# JOYSTICK_LED.net
KiCad netlist of a schematic drawn in Altium Designer
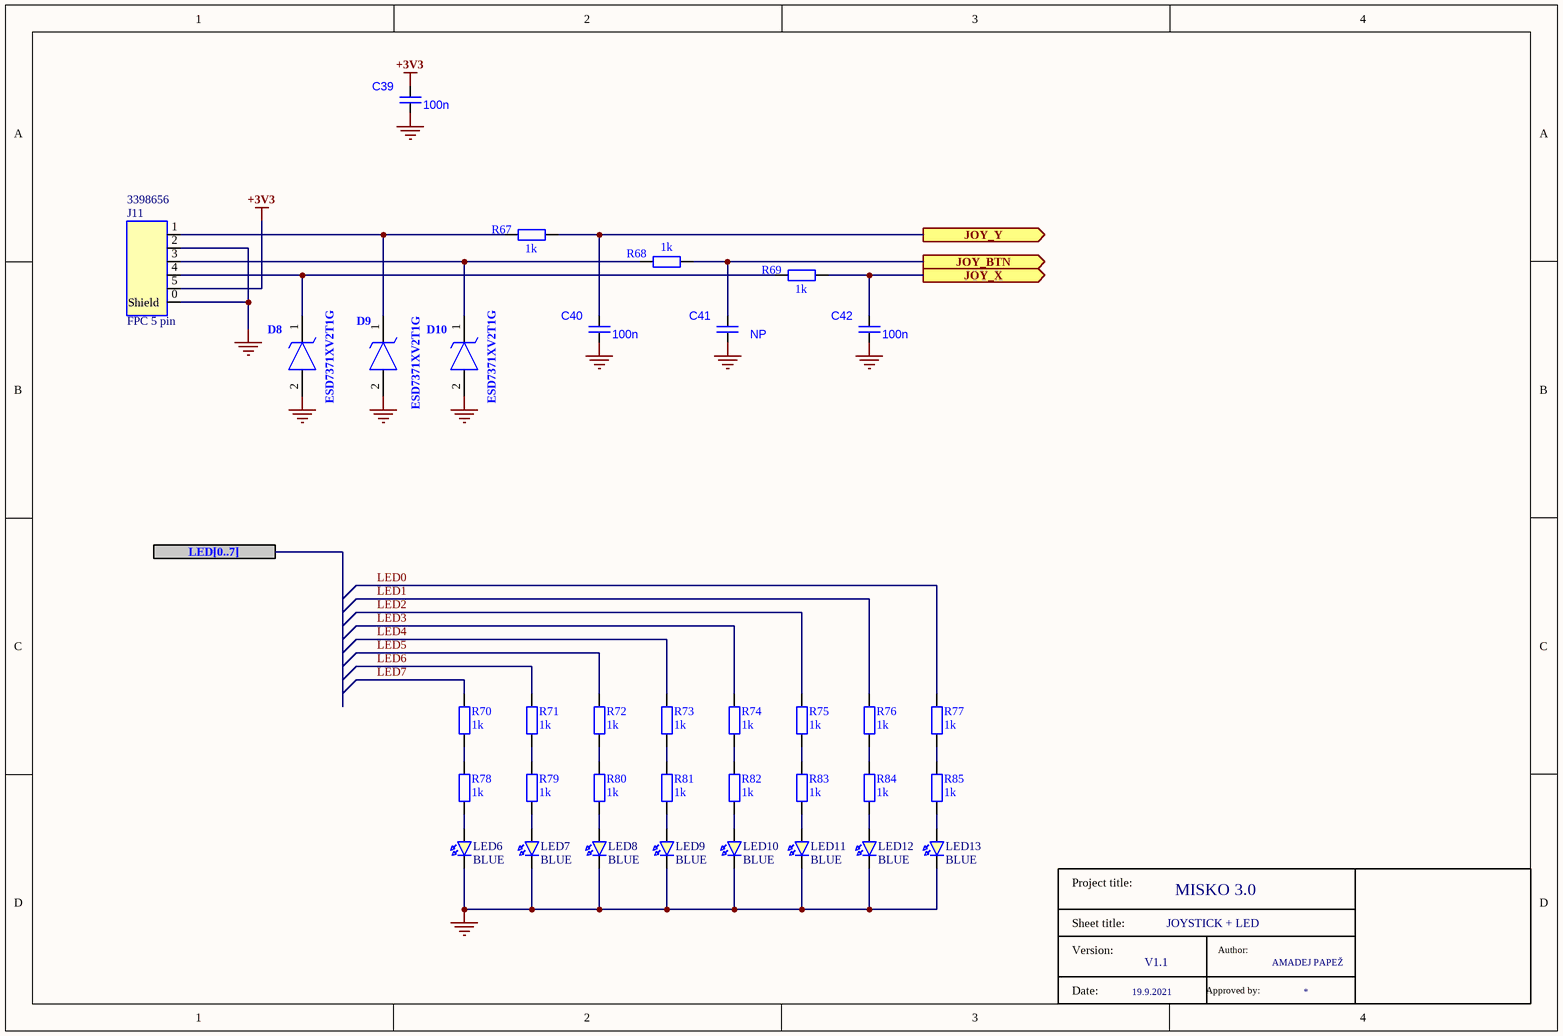
[diagram p0: JOYSTICK + LED.SchDoc]

(export (version "E")
  (design (tool "Eeschema 10.0.6"))
  (components
    (comp (ref "C39")
      (value "100n")
      (footprint "C0603")
      (description "Capacitor")
      (libsource (lib "MISKO3_V6") (part "C"))
    )
    (comp (ref "C40")
      (value "100n")
      (footprint "C0603")
      (description "Capacitor")
      (libsource (lib "MISKO3_V6") (part "C"))
    )
    (comp (ref "C41")
      (value "NP")
      (footprint "C0603")
      (description "Capacitor")
      (libsource (lib "MISKO3_V6") (part "C"))
    )
    (comp (ref "C42")
      (value "100n")
      (footprint "C0603")
      (description "Capacitor")
      (libsource (lib "MISKO3_V6") (part "C"))
    )
    (comp (ref "D8")
      (value "ESD7371XV2T1G")
      (footprint "SOD1608X70N")
      (description "TVS Diode (Uni-directional)")
      (fields (field (name "MOUSER PART NUMBER") "863-ESD7371XV2T1G"))
      (libsource (lib "MISKO3_V6") (part "ESD7371XV2T1G"))
    )
    (comp (ref "D9")
      (value "ESD7371XV2T1G")
      (footprint "SOD1608X70N")
      (description "TVS Diode (Uni-directional)")
      (fields (field (name "MOUSER PART NUMBER") "863-ESD7371XV2T1G"))
      (libsource (lib "MISKO3_V6") (part "ESD7371XV2T1G"))
    )
    (comp (ref "D10")
      (value "ESD7371XV2T1G")
      (footprint "SOD1608X70N")
      (description "TVS Diode (Uni-directional)")
      (fields (field (name "MOUSER PART NUMBER") "863-ESD7371XV2T1G"))
      (libsource (lib "MISKO3_V6") (part "ESD7371XV2T1G"))
    )
    (comp (ref "J11")
      (value "FPC 5 pin")
      (footprint "FPC 1734839-5")
      (description "TE connectivity  FPC 5 pin 0.5 mm ZIF top contact female connector 1734839-5")
      (fields (field (name "SUPPLIER PART NUMBER 1") "3398656"))
      (libsource (lib "MISKO3_V6") (part "FPC 1734839-5"))
    )
    (comp (ref "LED6")
      (value "BLUE")
      (footprint "LED1206")
      (description "LED")
      (libsource (lib "MISKO3_V6") (part "LED"))
    )
    (comp (ref "LED7")
      (value "BLUE")
      (footprint "LED1206")
      (description "LED")
      (libsource (lib "MISKO3_V6") (part "LED"))
    )
    (comp (ref "LED8")
      (value "BLUE")
      (footprint "LED1206")
      (description "LED")
      (libsource (lib "MISKO3_V6") (part "LED"))
    )
    (comp (ref "LED9")
      (value "BLUE")
      (footprint "LED1206")
      (description "LED")
      (libsource (lib "MISKO3_V6") (part "LED"))
    )
    (comp (ref "LED10")
      (value "BLUE")
      (footprint "LED1206")
      (description "LED")
      (libsource (lib "MISKO3_V6") (part "LED"))
    )
    (comp (ref "LED11")
      (value "BLUE")
      (footprint "LED1206")
      (description "LED")
      (libsource (lib "MISKO3_V6") (part "LED"))
    )
    (comp (ref "LED12")
      (value "BLUE")
      (footprint "LED1206")
      (description "LED")
      (libsource (lib "MISKO3_V6") (part "LED"))
    )
    (comp (ref "LED13")
      (value "BLUE")
      (footprint "LED1206")
      (description "LED")
      (libsource (lib "MISKO3_V6") (part "LED"))
    )
    (comp (ref "R67")
      (value "1k")
      (footprint "R1608_0603I_L")
      (description "R")
      (libsource (lib "MISKO3_V6") (part "R"))
    )
    (comp (ref "R68")
      (value "1k")
      (footprint "R1608_0603I_L")
      (description "R")
      (libsource (lib "MISKO3_V6") (part "R"))
    )
    (comp (ref "R69")
      (value "1k")
      (footprint "R1608_0603I_L")
      (description "R")
      (libsource (lib "MISKO3_V6") (part "R"))
    )
    (comp (ref "R70")
      (value "1k")
      (footprint "R1608_0603I_L")
      (description "R")
      (libsource (lib "MISKO3_V6") (part "R"))
    )
    (comp (ref "R71")
      (value "1k")
      (footprint "R1608_0603I_L")
      (description "R")
      (libsource (lib "MISKO3_V6") (part "R"))
    )
    (comp (ref "R72")
      (value "1k")
      (footprint "R1608_0603I_L")
      (description "R")
      (libsource (lib "MISKO3_V6") (part "R"))
    )
    (comp (ref "R73")
      (value "1k")
      (footprint "R1608_0603I_L")
      (description "R")
      (libsource (lib "MISKO3_V6") (part "R"))
    )
    (comp (ref "R74")
      (value "1k")
      (footprint "R1608_0603I_L")
      (description "R")
      (libsource (lib "MISKO3_V6") (part "R"))
    )
    (comp (ref "R75")
      (value "1k")
      (footprint "R1608_0603I_L")
      (description "R")
      (libsource (lib "MISKO3_V6") (part "R"))
    )
    (comp (ref "R76")
      (value "1k")
      (footprint "R1608_0603I_L")
      (description "R")
      (libsource (lib "MISKO3_V6") (part "R"))
    )
    (comp (ref "R77")
      (value "1k")
      (footprint "R1608_0603I_L")
      (description "R")
      (libsource (lib "MISKO3_V6") (part "R"))
    )
    (comp (ref "R78")
      (value "1k")
      (footprint "R1608_0603I_L")
      (description "R")
      (libsource (lib "MISKO3_V6") (part "R"))
    )
    (comp (ref "R79")
      (value "1k")
      (footprint "R1608_0603I_L")
      (description "R")
      (libsource (lib "MISKO3_V6") (part "R"))
    )
    (comp (ref "R80")
      (value "1k")
      (footprint "R1608_0603I_L")
      (description "R")
      (libsource (lib "MISKO3_V6") (part "R"))
    )
    (comp (ref "R81")
      (value "1k")
      (footprint "R1608_0603I_L")
      (description "R")
      (libsource (lib "MISKO3_V6") (part "R"))
    )
    (comp (ref "R82")
      (value "1k")
      (footprint "R1608_0603I_L")
      (description "R")
      (libsource (lib "MISKO3_V6") (part "R"))
    )
    (comp (ref "R83")
      (value "1k")
      (footprint "R1608_0603I_L")
      (description "R")
      (libsource (lib "MISKO3_V6") (part "R"))
    )
    (comp (ref "R84")
      (value "1k")
      (footprint "R1608_0603I_L")
      (description "R")
      (libsource (lib "MISKO3_V6") (part "R"))
    )
    (comp (ref "R85")
      (value "1k")
      (footprint "R1608_0603I_L")
      (description "R")
      (libsource (lib "MISKO3_V6") (part "R"))
    )
    (comp (ref "T9") (value "~") (libsource (lib "MISKO3_V6") (part "Title block")))
  )
  (nets
    (net (code "1") (name "+3V3") (class "Default")
      (node (ref "C39") (pin "2") (pinfunction "2_2") (pintype "passive"))
      (node (ref "J11") (pin "5") (pinfunction "5_5") (pintype "passive"))
    )
    (net (code "2") (name "/JOY_BTN") (class "Default")
      (node (ref "C41") (pin "2") (pinfunction "2_2") (pintype "passive"))
      (node (ref "R68") (pin "1") (pintype "passive"))
    )
    (net (code "3") (name "/JOY_X") (class "Default")
      (node (ref "C42") (pin "2") (pinfunction "2_2") (pintype "passive"))
      (node (ref "R69") (pin "1") (pintype "passive"))
    )
    (net (code "4") (name "/JOY_Y") (class "Default")
      (node (ref "C40") (pin "2") (pinfunction "2_2") (pintype "passive"))
      (node (ref "R67") (pin "1") (pintype "passive"))
    )
    (net (code "5") (name "/LED0") (class "Default") (node (ref "R77") (pin "2") (pintype "passive")))
    (net (code "6") (name "/LED1") (class "Default") (node (ref "R76") (pin "2") (pintype "passive")))
    (net (code "7") (name "/LED2") (class "Default") (node (ref "R75") (pin "2") (pintype "passive")))
    (net (code "8") (name "/LED3") (class "Default") (node (ref "R74") (pin "2") (pintype "passive")))
    (net (code "9") (name "/LED4") (class "Default") (node (ref "R73") (pin "2") (pintype "passive")))
    (net (code "10") (name "/LED5") (class "Default") (node (ref "R72") (pin "2") (pintype "passive")))
    (net (code "11") (name "/LED6") (class "Default") (node (ref "R71") (pin "2") (pintype "passive")))
    (net (code "12") (name "/LED7") (class "Default") (node (ref "R70") (pin "2") (pintype "passive")))
    (net (code "14") (name "GND") (class "Default")
      (node (ref "C39") (pin "1") (pinfunction "1_1") (pintype "passive"))
      (node (ref "C40") (pin "1") (pinfunction "1_1") (pintype "passive"))
      (node (ref "C41") (pin "1") (pinfunction "1_1") (pintype "passive"))
      (node (ref "C42") (pin "1") (pinfunction "1_1") (pintype "passive"))
      (node (ref "D10") (pin "2") (pinfunction "A_2") (pintype "passive"))
      (node (ref "D8") (pin "2") (pinfunction "A_2") (pintype "passive"))
      (node (ref "D9") (pin "2") (pinfunction "A_2") (pintype "passive"))
      (node (ref "J11") (pin "0") (pinfunction "Shield_0") (pintype "passive"))
      (node (ref "J11") (pin "2") (pinfunction "2_2") (pintype "passive"))
      (node (ref "LED10") (pin "1") (pinfunction "KATODE_1") (pintype "passive"))
      (node (ref "LED11") (pin "1") (pinfunction "KATODE_1") (pintype "passive"))
      (node (ref "LED12") (pin "1") (pinfunction "KATODE_1") (pintype "passive"))
      (node (ref "LED13") (pin "1") (pinfunction "KATODE_1") (pintype "passive"))
      (node (ref "LED6") (pin "1") (pinfunction "KATODE_1") (pintype "passive"))
      (node (ref "LED7") (pin "1") (pinfunction "KATODE_1") (pintype "passive"))
      (node (ref "LED8") (pin "1") (pinfunction "KATODE_1") (pintype "passive"))
      (node (ref "LED9") (pin "1") (pinfunction "KATODE_1") (pintype "passive"))
    )
    (net (code "15") (name "Net-(D8-K)") (class "Default")
      (node (ref "D8") (pin "1") (pinfunction "K_1") (pintype "passive"))
      (node (ref "J11") (pin "4") (pinfunction "4_4") (pintype "passive"))
      (node (ref "R69") (pin "2") (pintype "passive"))
    )
    (net (code "16") (name "Net-(D9-K)") (class "Default")
      (node (ref "D9") (pin "1") (pinfunction "K_1") (pintype "passive"))
      (node (ref "J11") (pin "1") (pinfunction "1_1") (pintype "passive"))
      (node (ref "R67") (pin "2") (pintype "passive"))
    )
    (net (code "17") (name "Net-(D10-K)") (class "Default")
      (node (ref "D10") (pin "1") (pinfunction "K_1") (pintype "passive"))
      (node (ref "J11") (pin "3") (pinfunction "3_3") (pintype "passive"))
      (node (ref "R68") (pin "2") (pintype "passive"))
    )
    (net (code "18") (name "Net-(LED6-ANODE)") (class "Default")
      (node (ref "LED6") (pin "2") (pinfunction "ANODE_2") (pintype "passive"))
      (node (ref "R78") (pin "1") (pintype "passive"))
    )
    (net (code "19") (name "Net-(LED7-ANODE)") (class "Default")
      (node (ref "LED7") (pin "2") (pinfunction "ANODE_2") (pintype "passive"))
      (node (ref "R79") (pin "1") (pintype "passive"))
    )
    (net (code "20") (name "Net-(LED8-ANODE)") (class "Default")
      (node (ref "LED8") (pin "2") (pinfunction "ANODE_2") (pintype "passive"))
      (node (ref "R80") (pin "1") (pintype "passive"))
    )
    (net (code "21") (name "Net-(LED9-ANODE)") (class "Default")
      (node (ref "LED9") (pin "2") (pinfunction "ANODE_2") (pintype "passive"))
      (node (ref "R81") (pin "1") (pintype "passive"))
    )
    (net (code "22") (name "Net-(LED10-ANODE)") (class "Default")
      (node (ref "LED10") (pin "2") (pinfunction "ANODE_2") (pintype "passive"))
      (node (ref "R82") (pin "1") (pintype "passive"))
    )
    (net (code "23") (name "Net-(LED11-ANODE)") (class "Default")
      (node (ref "LED11") (pin "2") (pinfunction "ANODE_2") (pintype "passive"))
      (node (ref "R83") (pin "1") (pintype "passive"))
    )
    (net (code "24") (name "Net-(LED12-ANODE)") (class "Default")
      (node (ref "LED12") (pin "2") (pinfunction "ANODE_2") (pintype "passive"))
      (node (ref "R84") (pin "1") (pintype "passive"))
    )
    (net (code "25") (name "Net-(LED13-ANODE)") (class "Default")
      (node (ref "LED13") (pin "2") (pinfunction "ANODE_2") (pintype "passive"))
      (node (ref "R85") (pin "1") (pintype "passive"))
    )
    (net (code "26") (name "Net-(R70-Pad1)") (class "Default")
      (node (ref "R70") (pin "1") (pintype "passive"))
      (node (ref "R78") (pin "2") (pintype "passive"))
    )
    (net (code "27") (name "Net-(R71-Pad1)") (class "Default")
      (node (ref "R71") (pin "1") (pintype "passive"))
      (node (ref "R79") (pin "2") (pintype "passive"))
    )
    (net (code "28") (name "Net-(R72-Pad1)") (class "Default")
      (node (ref "R72") (pin "1") (pintype "passive"))
      (node (ref "R80") (pin "2") (pintype "passive"))
    )
    (net (code "29") (name "Net-(R73-Pad1)") (class "Default")
      (node (ref "R73") (pin "1") (pintype "passive"))
      (node (ref "R81") (pin "2") (pintype "passive"))
    )
    (net (code "30") (name "Net-(R74-Pad1)") (class "Default")
      (node (ref "R74") (pin "1") (pintype "passive"))
      (node (ref "R82") (pin "2") (pintype "passive"))
    )
    (net (code "31") (name "Net-(R75-Pad1)") (class "Default")
      (node (ref "R75") (pin "1") (pintype "passive"))
      (node (ref "R83") (pin "2") (pintype "passive"))
    )
    (net (code "32") (name "Net-(R76-Pad1)") (class "Default")
      (node (ref "R76") (pin "1") (pintype "passive"))
      (node (ref "R84") (pin "2") (pintype "passive"))
    )
    (net (code "33") (name "Net-(R77-Pad1)") (class "Default")
      (node (ref "R77") (pin "1") (pintype "passive"))
      (node (ref "R85") (pin "2") (pintype "passive"))
    )
  )
)
